# PoBoV1.net
KiCad netlist of a schematic drawn in EAGLE
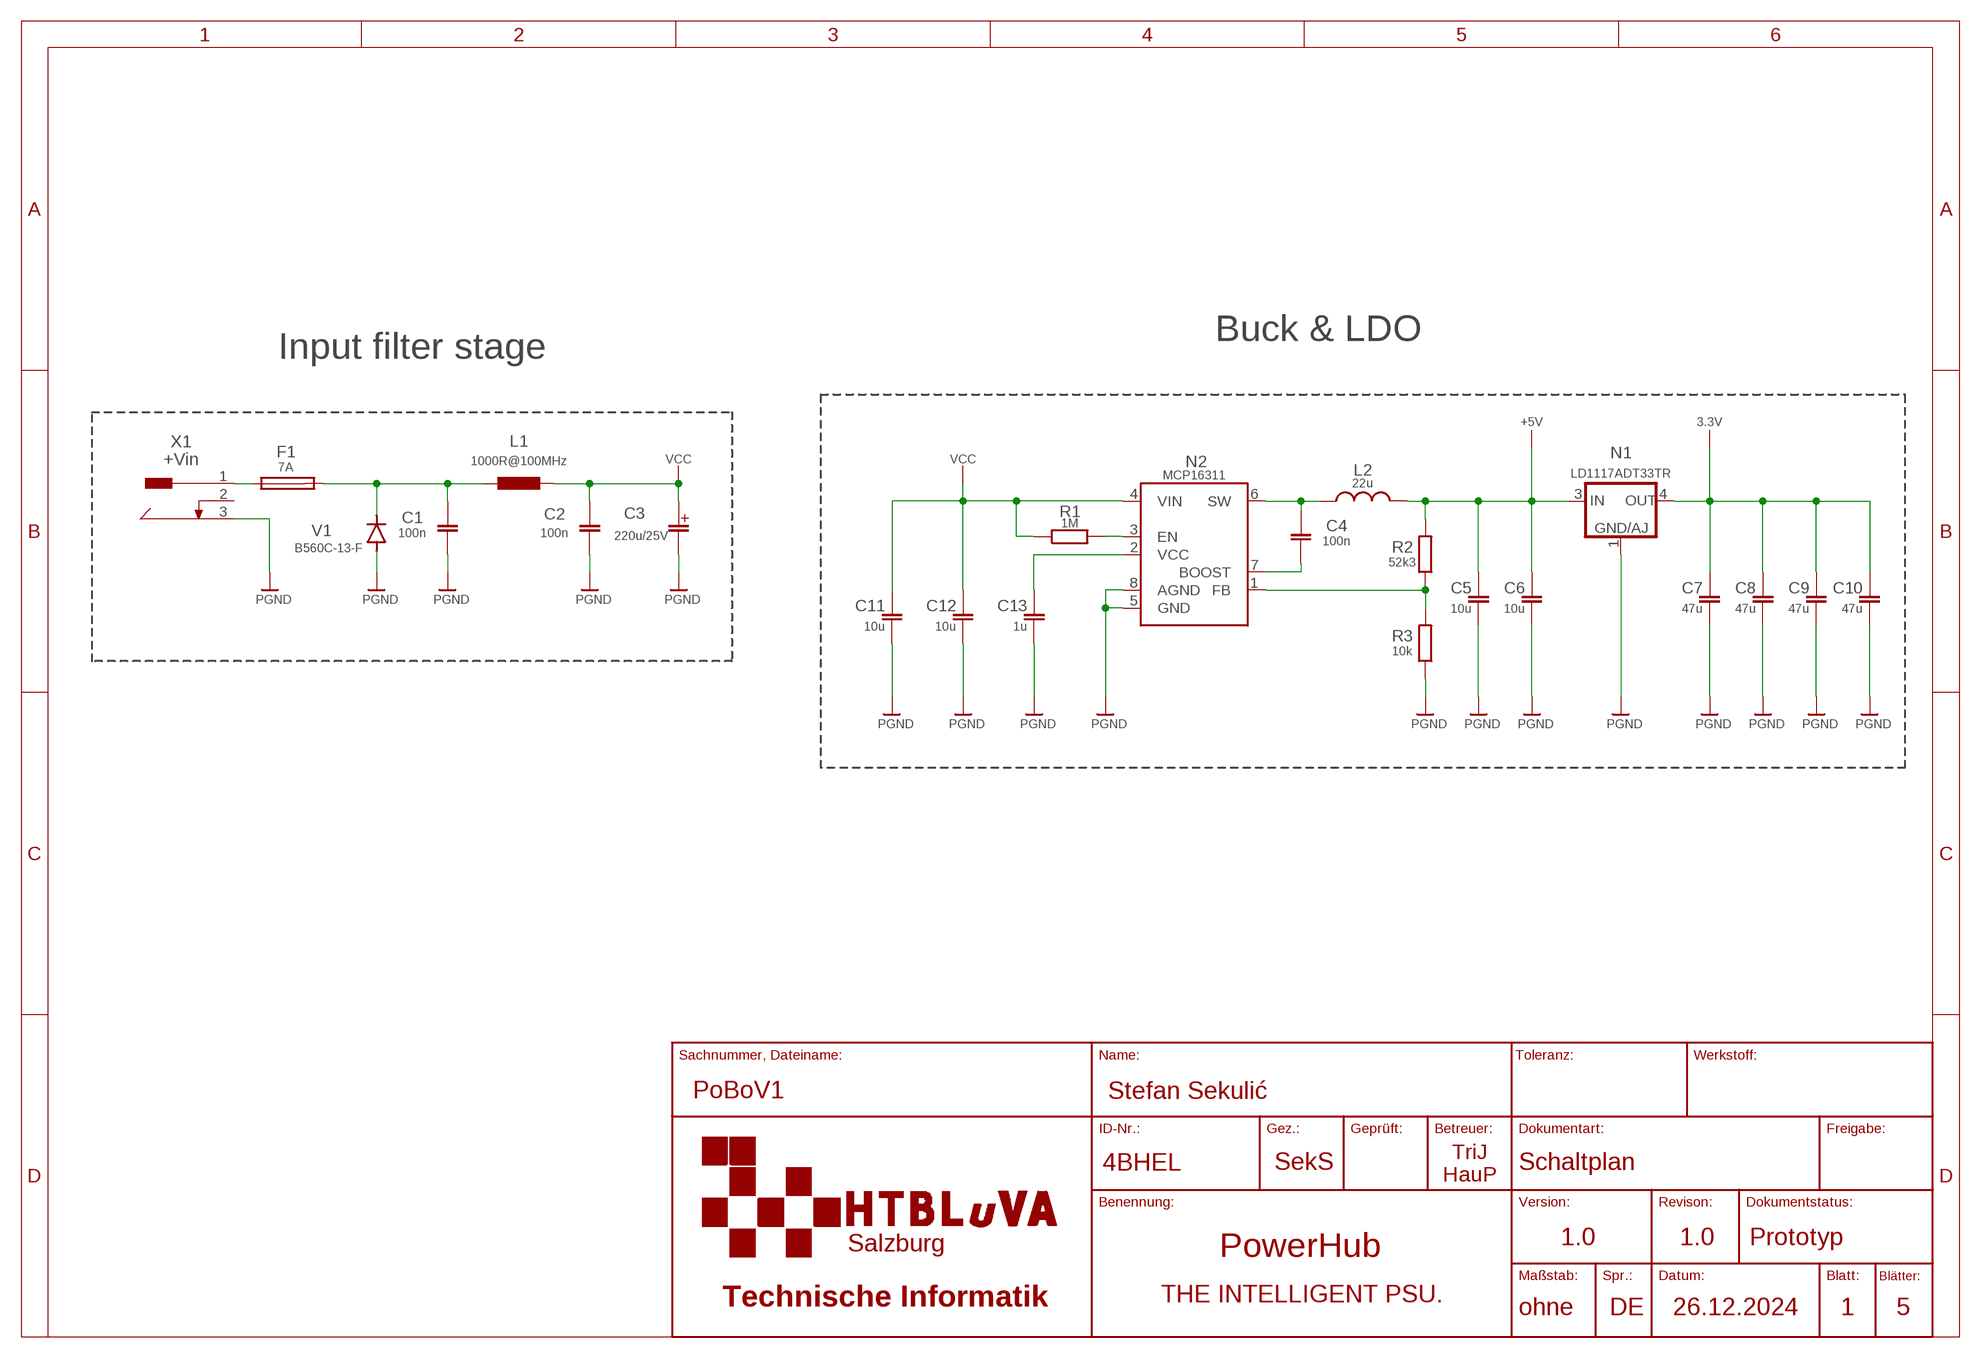
[diagram p0: schematic, sheet 1]
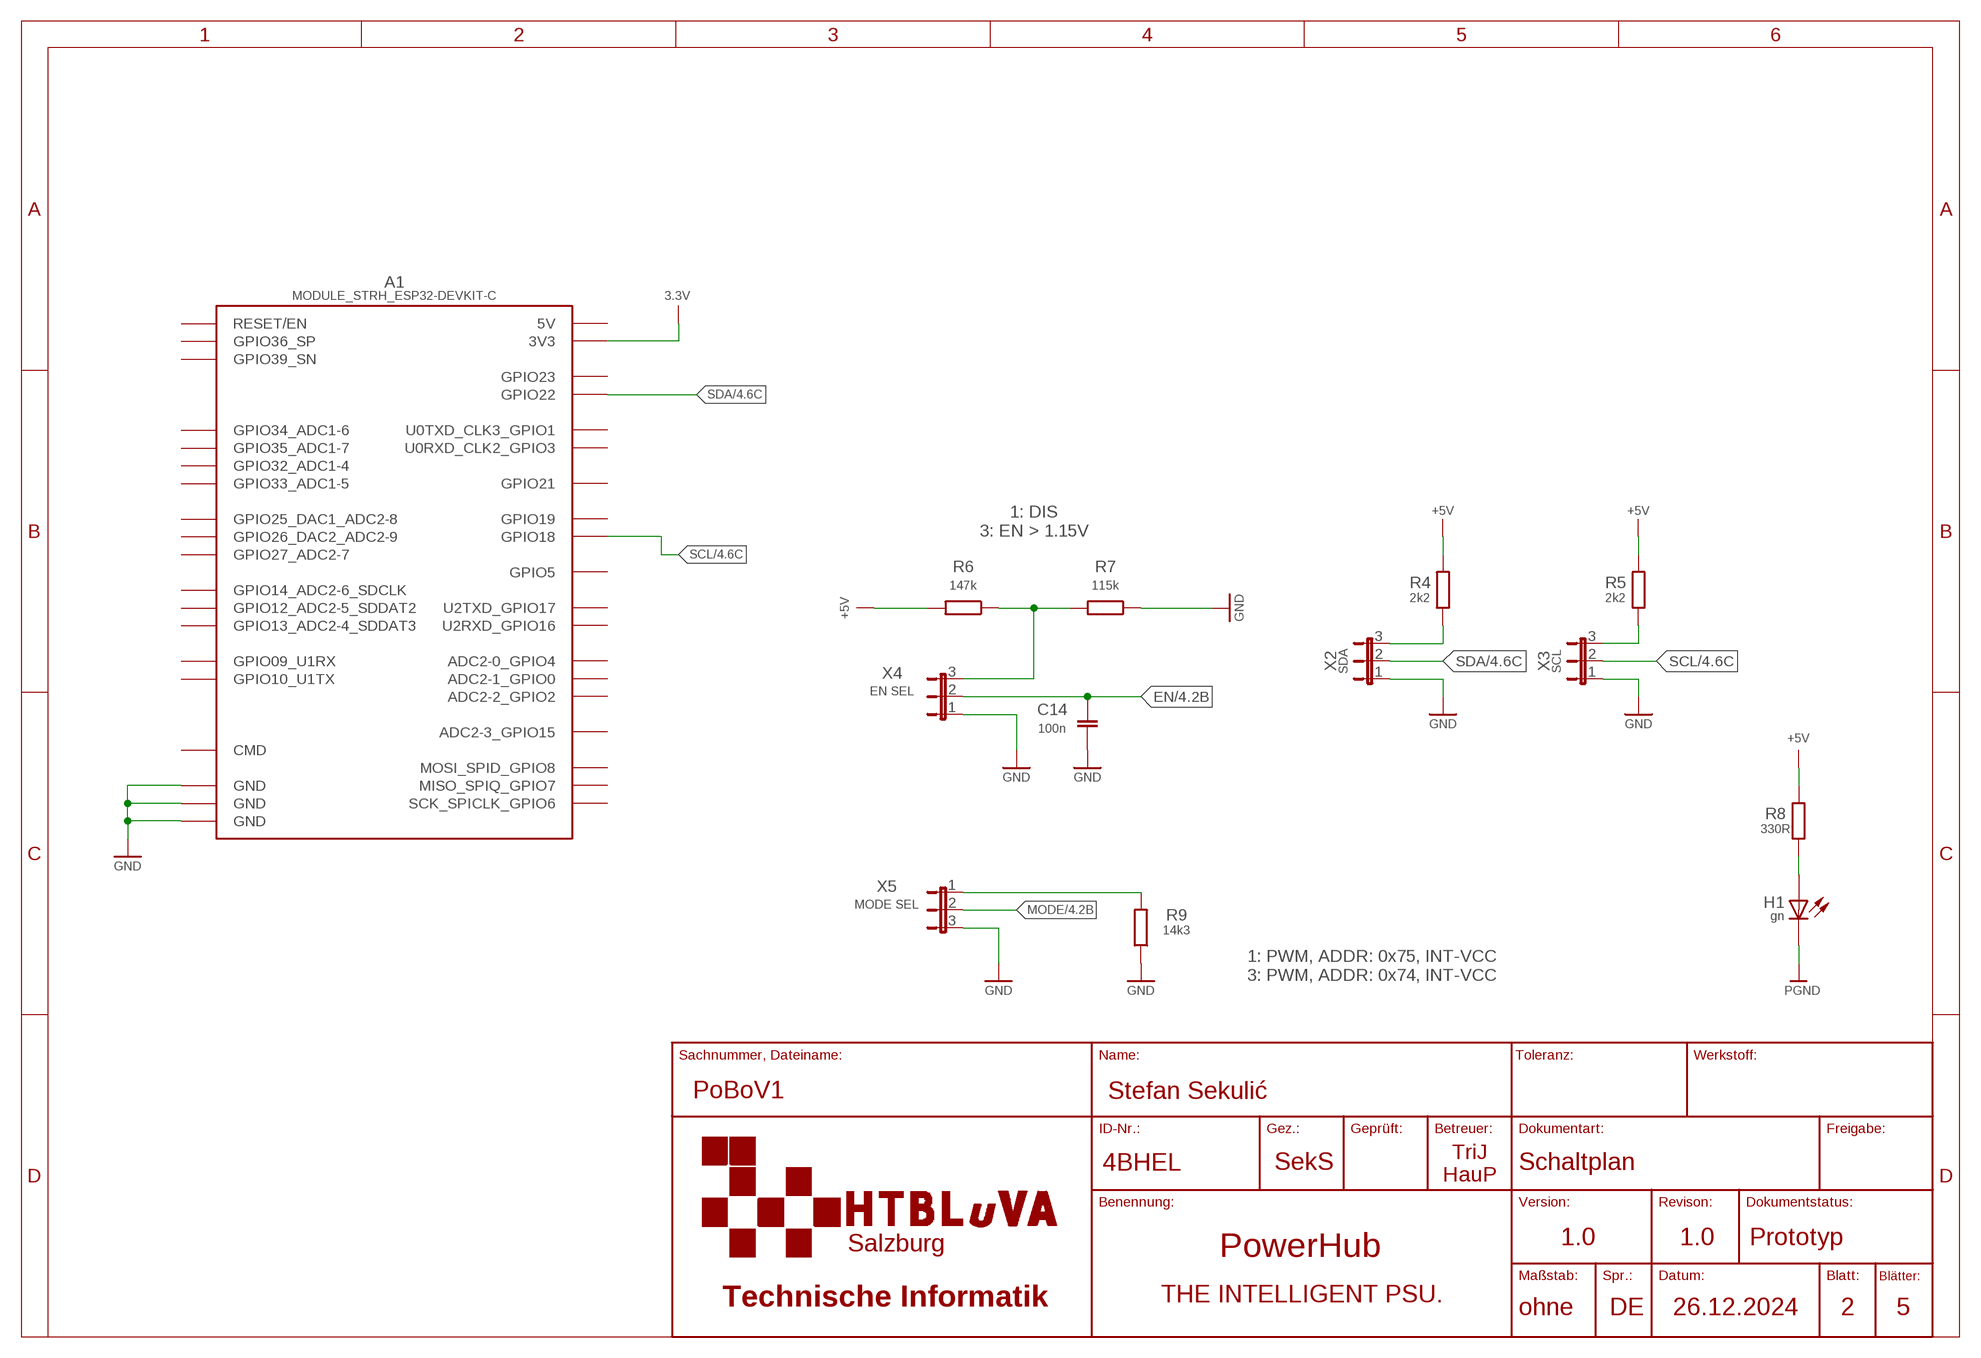
[diagram p1: schematic, sheet 2]
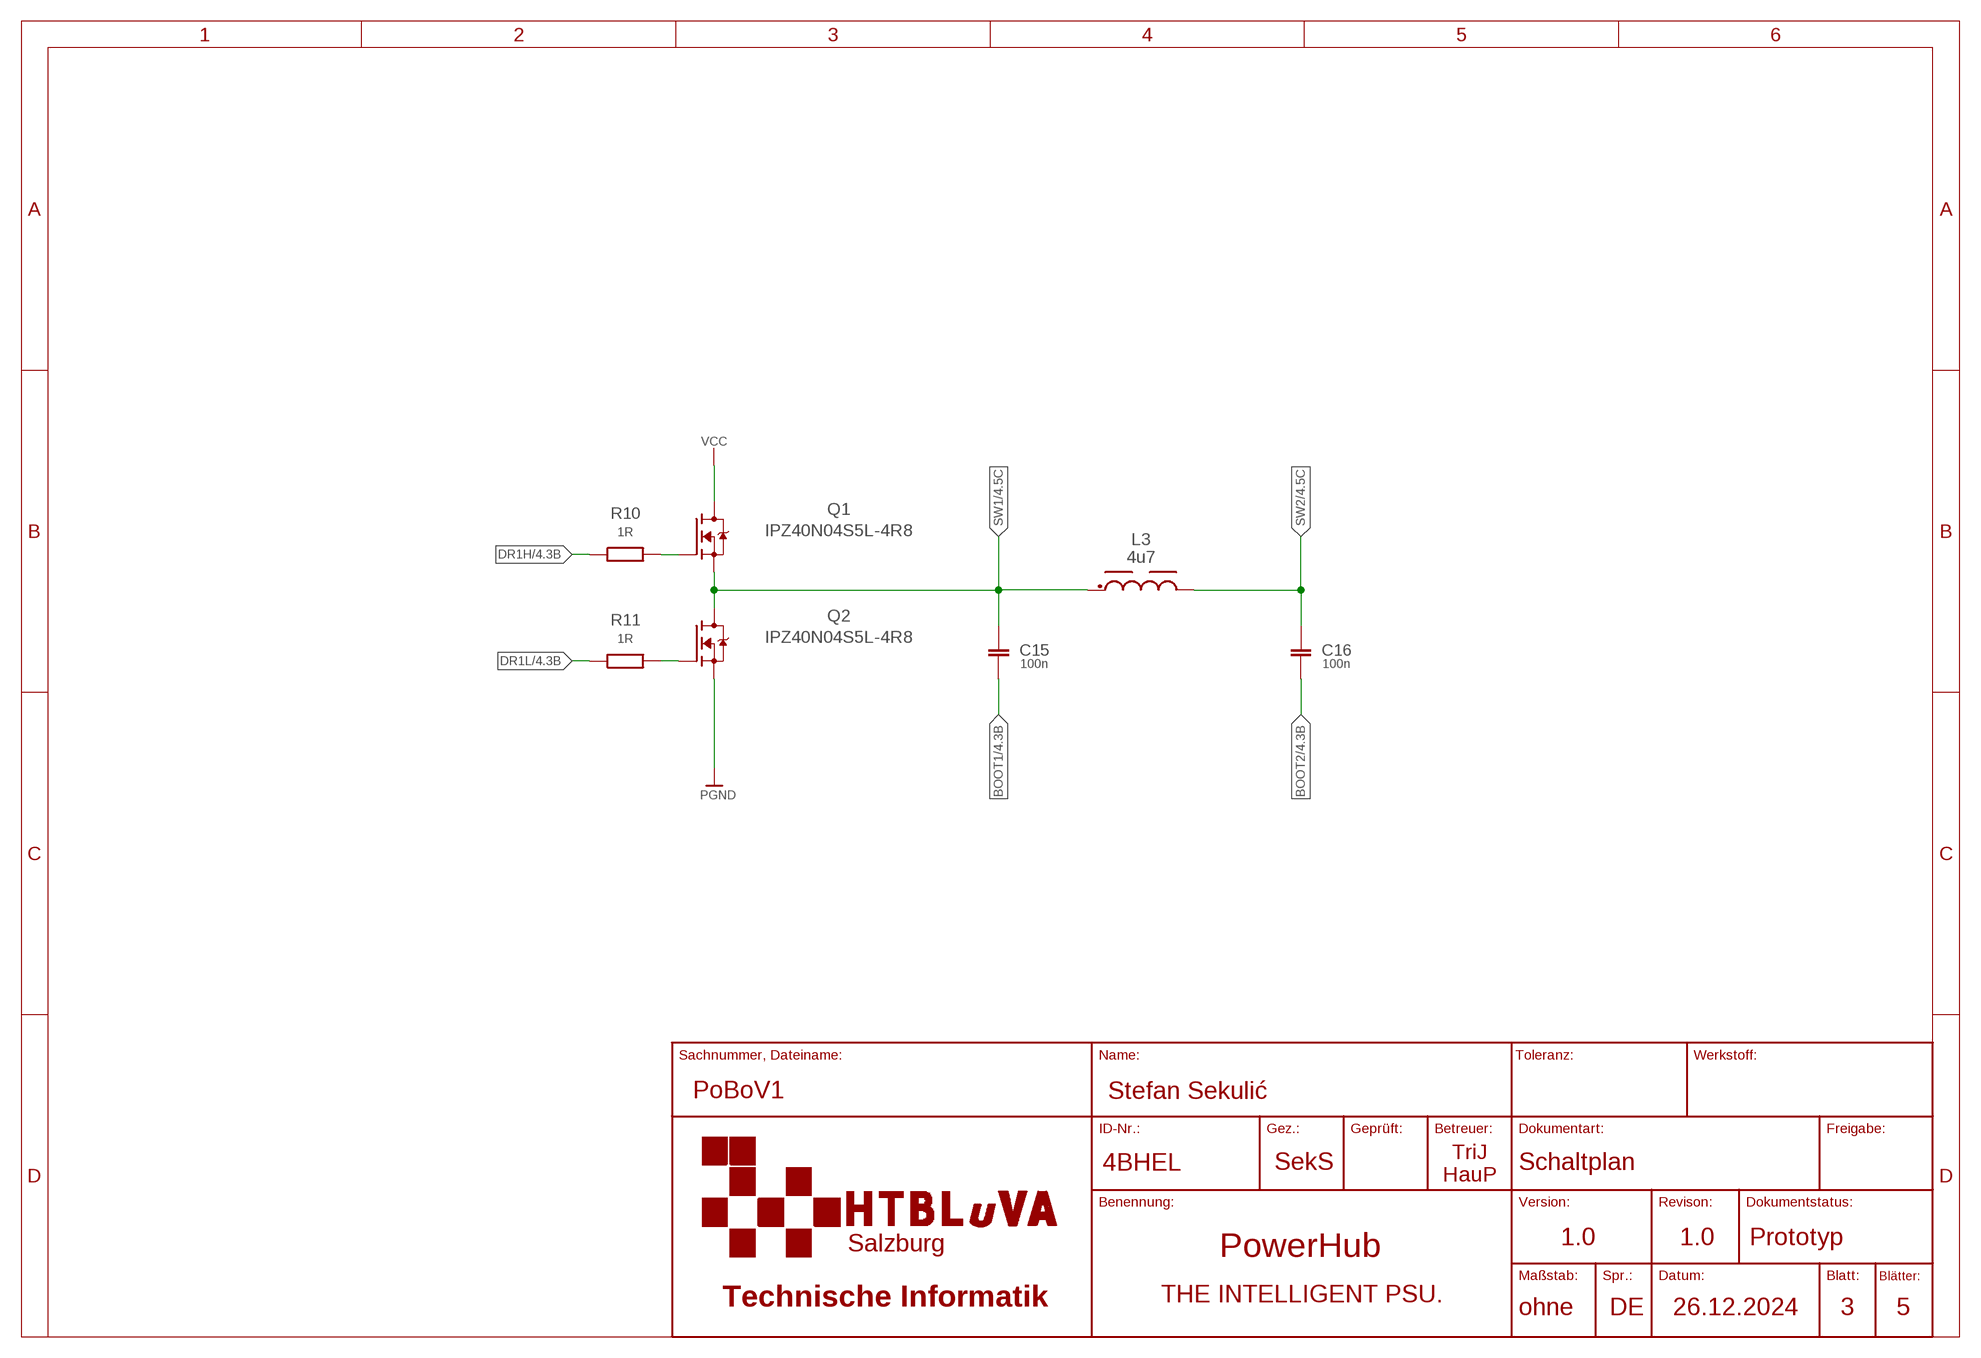
[diagram p2: schematic, sheet 3]
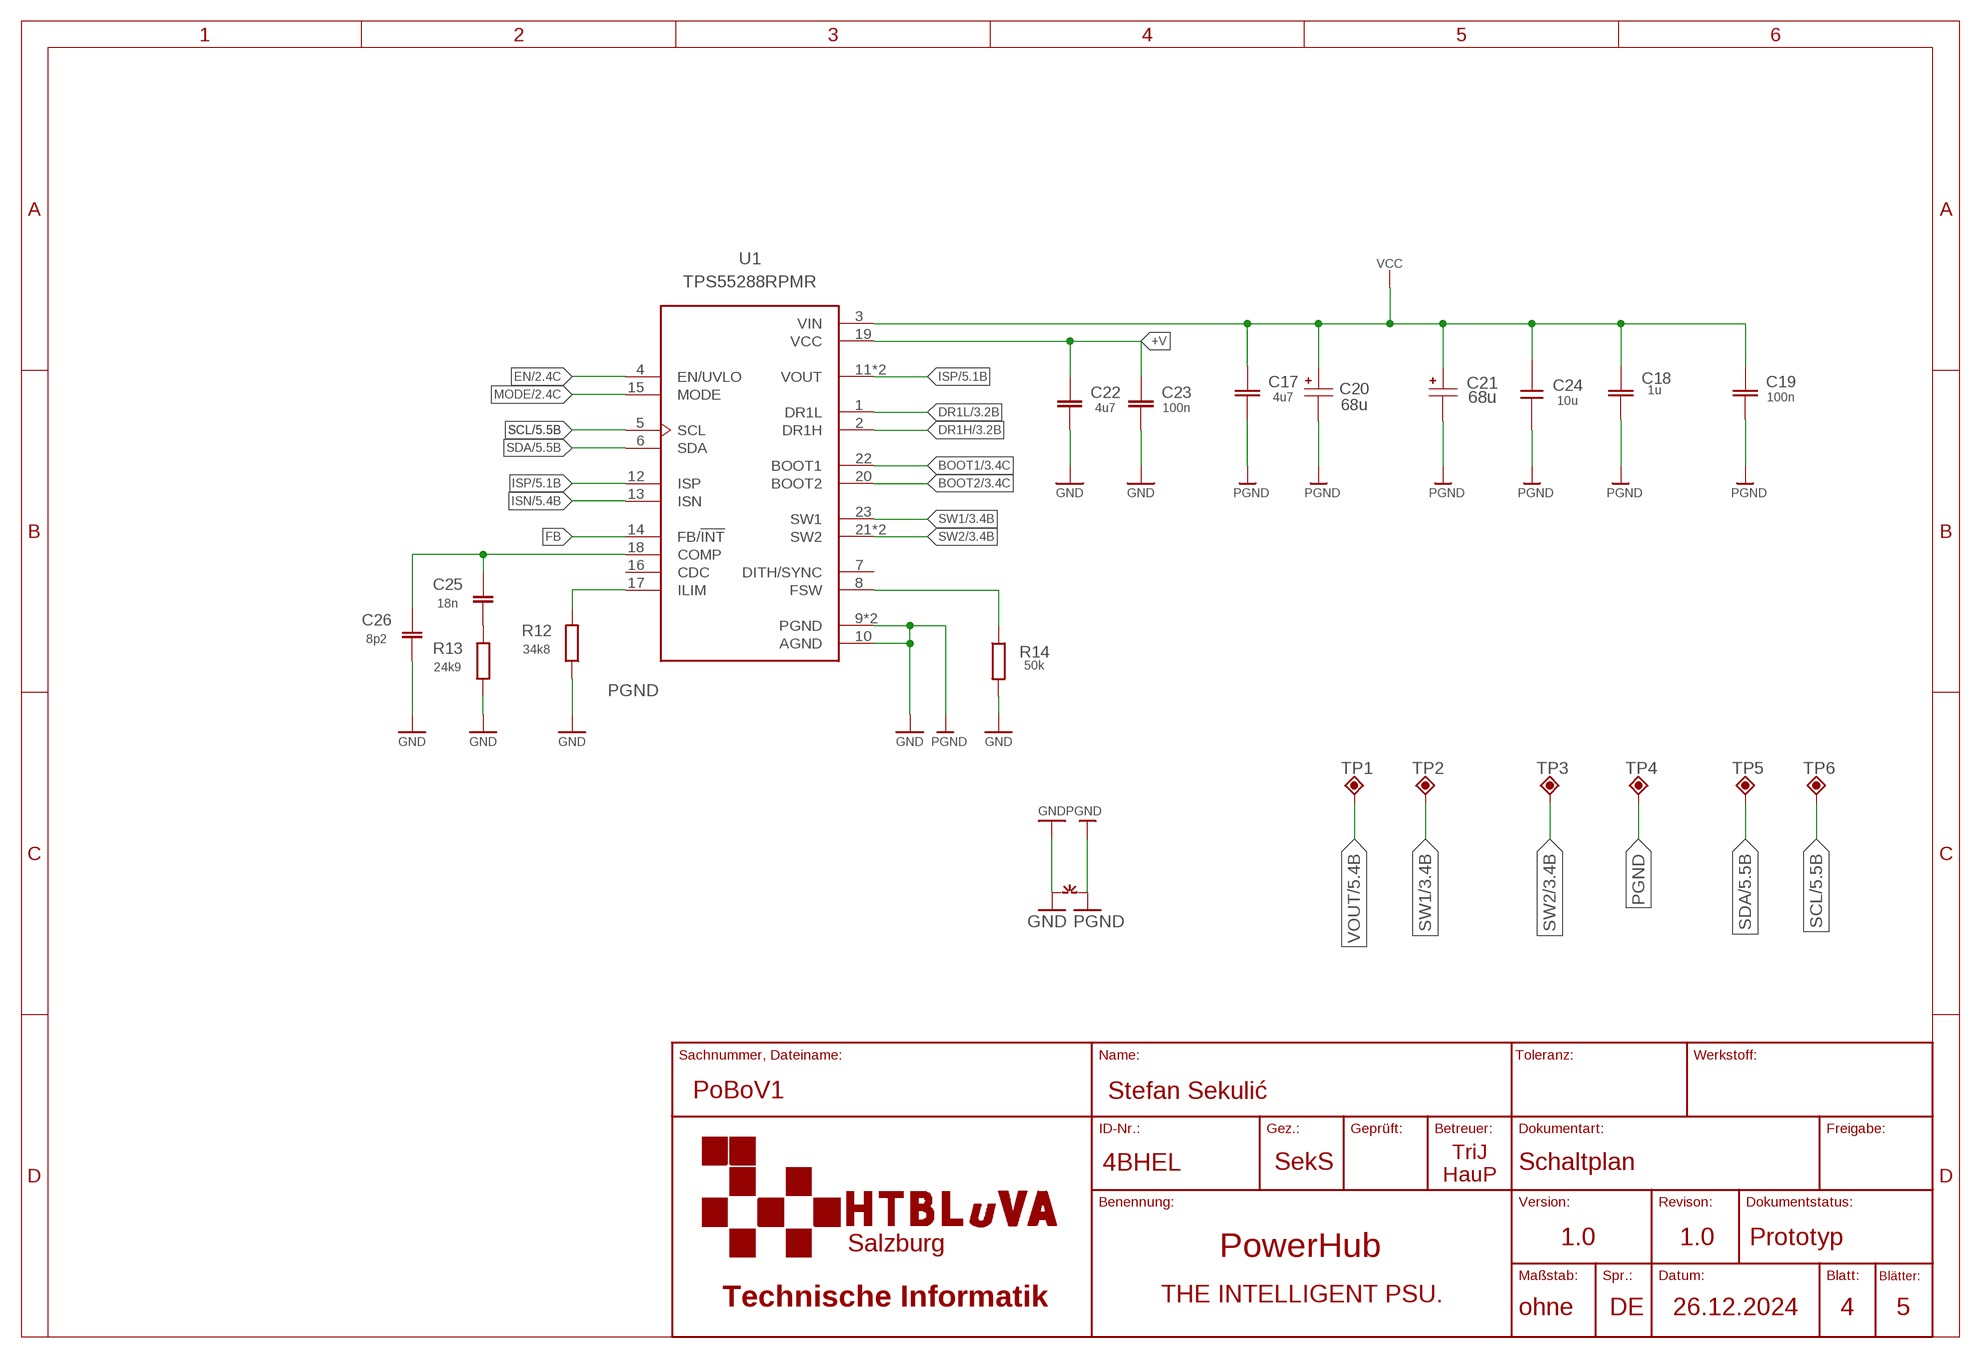
[diagram p3: schematic, sheet 4]
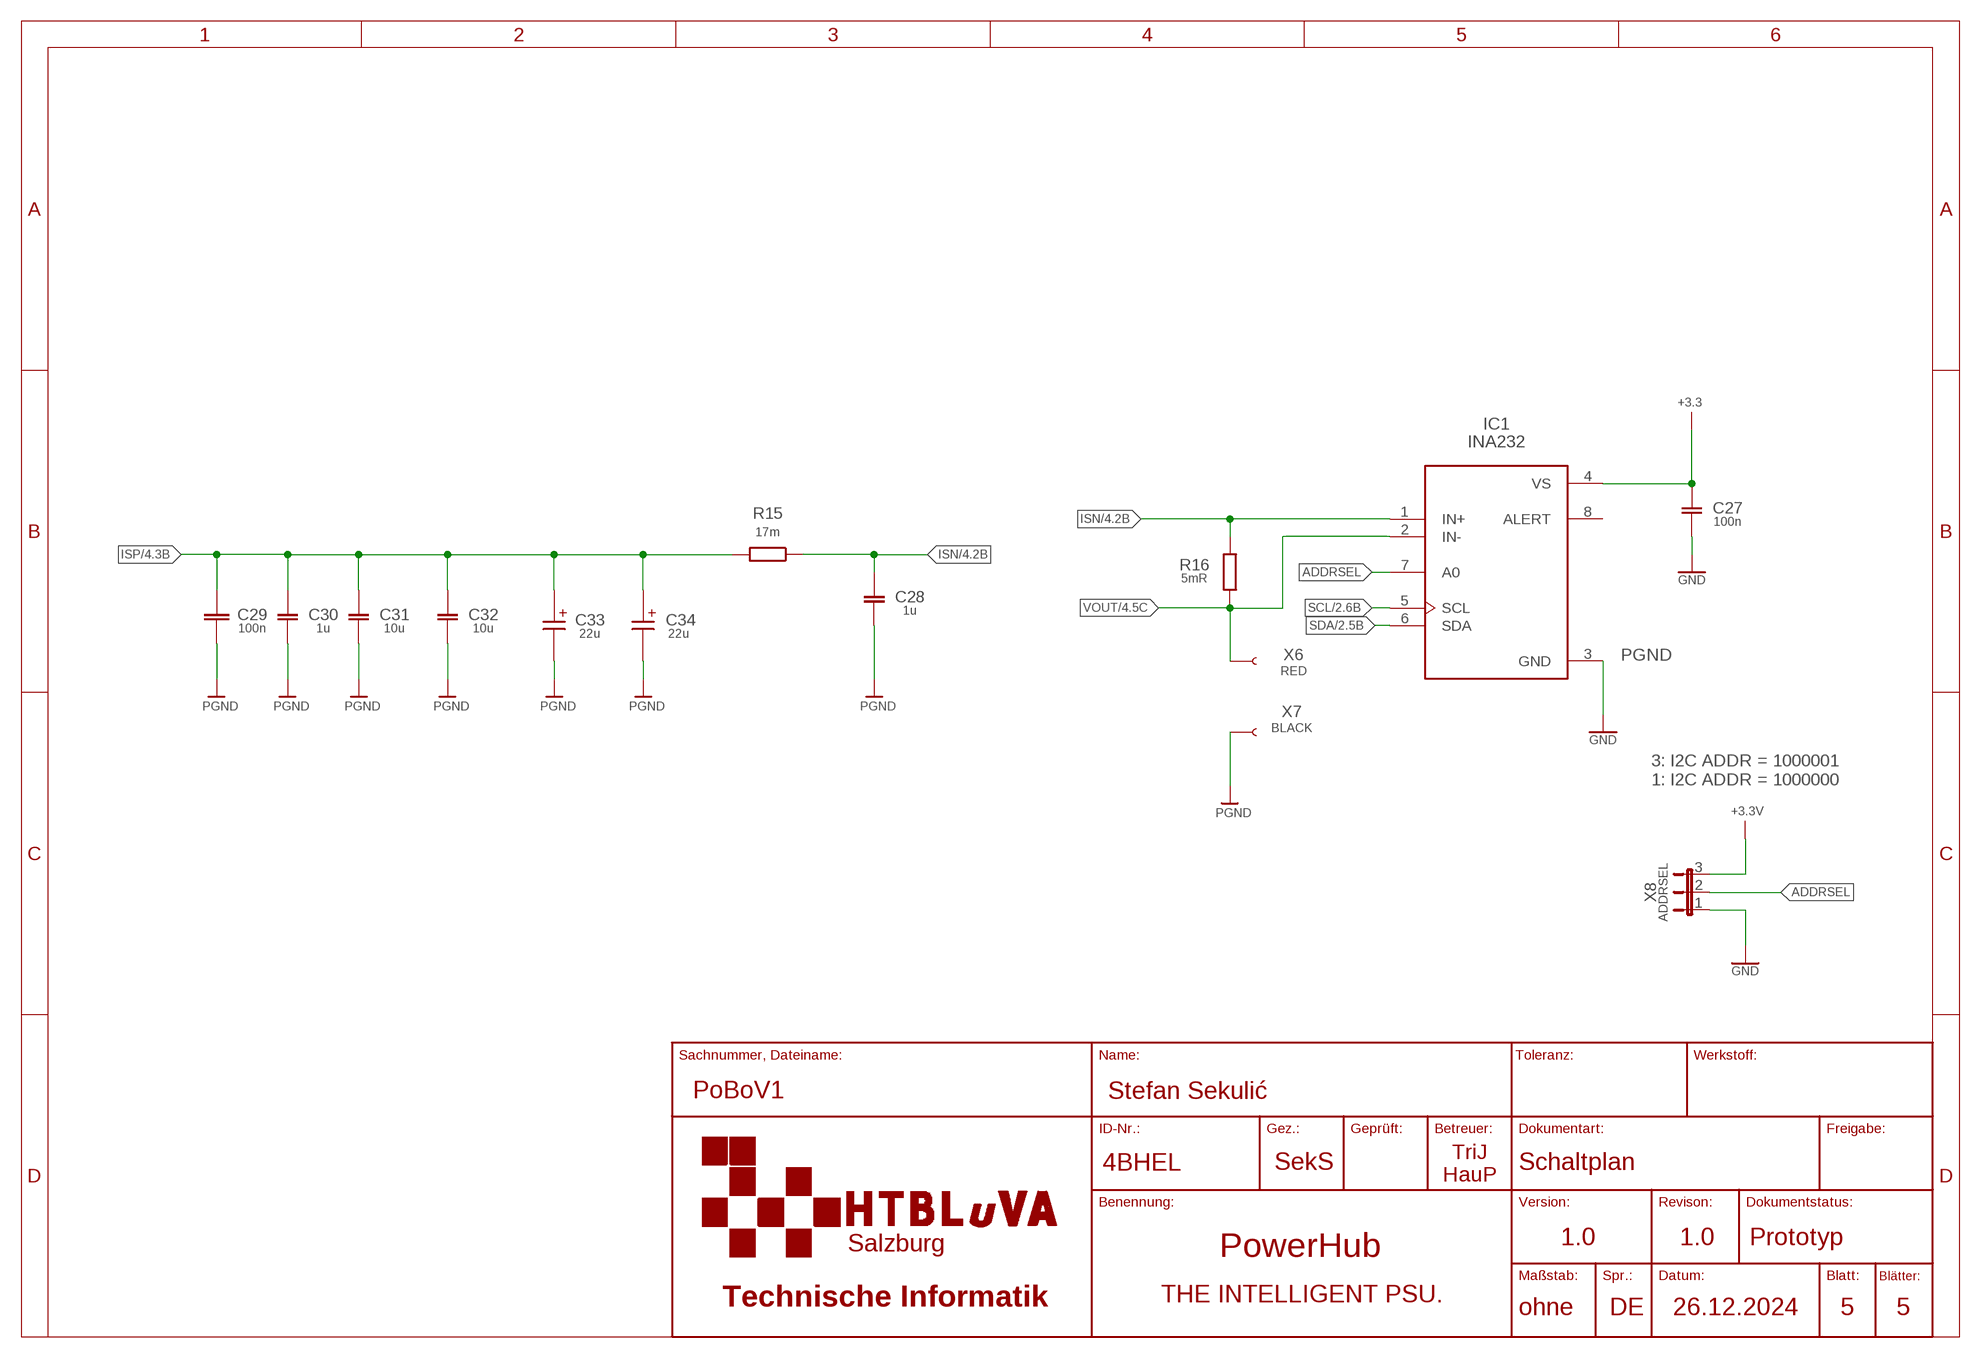
[diagram p4: schematic, sheet 5]

(export (version "E")
  (design (tool "Eeschema 10.0.6"))
  (components
    (comp (ref "C27")
      (value "100n")
      (footprint "eagle-import:MYLIB_C0805")
      (libsource (lib "eagle-import") (part "C-EUC0805"))
    )
    (comp (ref "C28")
      (value "1u")
      (footprint "eagle-import:MYLIB_C0805")
      (libsource (lib "eagle-import") (part "C-EUC0805"))
    )
    (comp (ref "C29")
      (value "100n")
      (footprint "eagle-import:MYRCL_C0402")
      (libsource (lib "eagle-import") (part "RCL_C-EUC0402"))
    )
    (comp (ref "C30")
      (value "1u")
      (footprint "eagle-import:MYLIB_C0805")
      (libsource (lib "eagle-import") (part "C-EUC0805"))
    )
    (comp (ref "C31")
      (value "10u")
      (footprint "eagle-import:MYLIB_C0805")
      (libsource (lib "eagle-import") (part "C-EUC0805"))
    )
    (comp (ref "C32")
      (value "10u")
      (footprint "eagle-import:MYLIB_C0805")
      (libsource (lib "eagle-import") (part "C-EUC0805"))
    )
    (comp (ref "C33")
      (value "22u")
      (footprint "eagle-import:PANASONIC_G")
      (libsource (lib "eagle-import") (part "C-POL_G"))
    )
    (comp (ref "C34")
      (value "22u")
      (footprint "eagle-import:PANASONIC_G")
      (libsource (lib "eagle-import") (part "C-POL_G"))
    )
    (comp (ref "IC1")
      (value "INA232")
      (footprint "eagle-import:SOT65P280X110-8N")
      (fields (field (name "MF") "Texas Instruments") (field (name "MP") "INA232AIDDFR"))
      (libsource (lib "eagle-import") (part "INA232AIDDFR"))
    )
    (comp (ref "R15")
      (value "17m")
      (footprint "eagle-import:R0805")
      (libsource (lib "eagle-import") (part "R-EU_R0805"))
    )
    (comp (ref "R16")
      (value "5mR")
      (footprint "eagle-import:RCL_STRH_R0805")
      (libsource (lib "eagle-import") (part "RCL_STRH_R-EU_R0805"))
    )
    (comp (ref "X6")
      (value "RED")
      (footprint "eagle-import:BANANAJACK")
      (libsource (lib "eagle-import") (part "BANANAJACKBANANAJACK-RED"))
    )
    (comp (ref "X7")
      (value "BLACK")
      (footprint "eagle-import:BANANAJACK")
      (libsource (lib "eagle-import") (part "BANANAJACKBANANAJACK-BLACK"))
    )
    (comp (ref "X8")
      (value "ADDRSEL")
      (footprint "eagle-import:JUMPER_JP3")
      (libsource (lib "eagle-import") (part "StefNe555_JUMPER_JP3EJP3E"))
    )
    (comp (ref "A1")
      (value "MODULE_STRH_ESP32-DEVKIT-C")
      (footprint "eagle-import:MODULE_STRH_DIL38-10_ESP")
      (libsource (lib "eagle-import") (part "MODULE_STRH_ESP32-DEVKIT-C"))
    )
    (comp (ref "C14")
      (value "100n")
      (footprint "eagle-import:C0805")
      (libsource (lib "eagle-import") (part "rcl_STRH_C-EUC0805"))
    )
    (comp (ref "H1")
      (value "gn")
      (footprint "eagle-import:CHIPLED_0805")
      (libsource (lib "eagle-import") (part "LEDCHIPLED_0805"))
    )
    (comp (ref "R4")
      (value "2k2")
      (footprint "eagle-import:R0805")
      (libsource (lib "eagle-import") (part "rcl_STRH_R-EU_R0805"))
    )
    (comp (ref "R5")
      (value "2k2")
      (footprint "eagle-import:R0805")
      (libsource (lib "eagle-import") (part "rcl_STRH_R-EU_R0805"))
    )
    (comp (ref "R6")
      (value "147k")
      (footprint "eagle-import:R0805")
      (libsource (lib "eagle-import") (part "rcl_STRH_R-EU_R0805"))
    )
    (comp (ref "R7")
      (value "115k")
      (footprint "eagle-import:R0805")
      (libsource (lib "eagle-import") (part "rcl_STRH_R-EU_R0805"))
    )
    (comp (ref "R8")
      (value "330R")
      (footprint "eagle-import:R0805")
      (libsource (lib "eagle-import") (part "rcl_STRH_R-EU_R0805"))
    )
    (comp (ref "R9")
      (value "14k3")
      (footprint "eagle-import:R0805")
      (libsource (lib "eagle-import") (part "rcl_STRH_R-EU_R0805"))
    )
    (comp (ref "X2")
      (value "SDA")
      (footprint "eagle-import:JUMPER_JP3")
      (libsource (lib "eagle-import") (part "JUMPER_JP3EJP3E"))
    )
    (comp (ref "X3")
      (value "SCL")
      (footprint "eagle-import:JUMPER_JP3")
      (libsource (lib "eagle-import") (part "JUMPER_JP3EJP3E"))
    )
    (comp (ref "X4")
      (value "EN SEL")
      (footprint "eagle-import:JUMPER_JP3")
      (libsource (lib "eagle-import") (part "JUMPER_JP3EJP3E"))
    )
    (comp (ref "X5")
      (value "MODE SEL")
      (footprint "eagle-import:JUMPER_JP3")
      (libsource (lib "eagle-import") (part "JUMPER_JP3EJP3E"))
    )
    (comp (ref "C17")
      (value "4u7")
      (footprint "eagle-import:MYRCL_C0603")
      (libsource (lib "eagle-import") (part "RCL_C-EUC0603"))
    )
    (comp (ref "C18")
      (value "1u")
      (footprint "eagle-import:MYRCL_C0603K")
      (libsource (lib "eagle-import") (part "RCL_C-EUC0603K"))
    )
    (comp (ref "C19")
      (value "100n")
      (footprint "eagle-import:MYRCL_C0402")
      (libsource (lib "eagle-import") (part "RCL_C-EUC0402"))
    )
    (comp (ref "C20")
      (value "68u")
      (footprint "eagle-import:CAP_EEHZA1H680P")
      (fields (field (name "MF") "Panasonic Electronic") (field (name "MP") "EEH-ZA1H680P"))
      (libsource (lib "eagle-import") (part "EEHZA1H680P"))
    )
    (comp (ref "C21")
      (value "68u")
      (footprint "eagle-import:CAP_EEHZA1H680P")
      (fields (field (name "MF") "Panasonic Electronic") (field (name "MP") "EEH-ZA1H680P"))
      (libsource (lib "eagle-import") (part "EEHZA1H680P"))
    )
    (comp (ref "C22")
      (value "4u7")
      (footprint "eagle-import:MYRCL_C0603")
      (libsource (lib "eagle-import") (part "RCL_C-EUC0603"))
    )
    (comp (ref "C23")
      (value "100n")
      (footprint "eagle-import:MYRCL_C0603")
      (libsource (lib "eagle-import") (part "RCL_C-EUC0603"))
    )
    (comp (ref "C24")
      (value "10u")
      (footprint "eagle-import:C1210")
      (libsource (lib "eagle-import") (part "C-EU_C1210"))
    )
    (comp (ref "C25")
      (value "18n")
      (footprint "eagle-import:MYLIB_C0805")
      (libsource (lib "eagle-import") (part "C-EUC0805"))
    )
    (comp (ref "C26")
      (value "8p2")
      (footprint "eagle-import:MYLIB_C0805")
      (libsource (lib "eagle-import") (part "C-EUC0805"))
    )
    (comp (ref "R12")
      (value "34k8")
      (footprint "eagle-import:R0805")
      (libsource (lib "eagle-import") (part "R-EU_R0805"))
    )
    (comp (ref "R13")
      (value "24k9")
      (footprint "eagle-import:R0805")
      (libsource (lib "eagle-import") (part "R-EU_R0805"))
    )
    (comp (ref "R14")
      (value "50k")
      (footprint "eagle-import:R0805")
      (libsource (lib "eagle-import") (part "R-EU_R0805"))
    )
    (comp (ref "TP1")
      (value "TPP-SMD-20SN")
      (footprint "eagle-import:SMD-20SN")
      (libsource (lib "eagle-import") (part "TPP-SMD-20SN"))
    )
    (comp (ref "TP2")
      (value "TPP-SMD-20SN")
      (footprint "eagle-import:SMD-20SN")
      (libsource (lib "eagle-import") (part "TPP-SMD-20SN"))
    )
    (comp (ref "TP3")
      (value "TPP-SMD-20SN")
      (footprint "eagle-import:SMD-20SN")
      (libsource (lib "eagle-import") (part "TPP-SMD-20SN"))
    )
    (comp (ref "TP4")
      (value "TPP-SMD-20SN")
      (footprint "eagle-import:SMD-20SN")
      (libsource (lib "eagle-import") (part "TPP-SMD-20SN"))
    )
    (comp (ref "TP5")
      (value "TPP-SMD-20SN")
      (footprint "eagle-import:SMD-20SN")
      (libsource (lib "eagle-import") (part "TPP-SMD-20SN"))
    )
    (comp (ref "TP6")
      (value "TPP-SMD-20SN")
      (footprint "eagle-import:SMD-20SN")
      (libsource (lib "eagle-import") (part "TPP-SMD-20SN"))
    )
    (comp (ref "U1")
      (value "TPS55288RPMR")
      (footprint "eagle-import:IC_TPS55288RPMR")
      (fields (field (name "MF") "Texas Instruments"))
      (libsource (lib "eagle-import") (part "TPS55288RPMR"))
    )
    (comp (ref "~NUDEV~1")
      (value "GND-GNDA")
      (footprint "eagle-import:GND-GNDA")
      (libsource (lib "eagle-import") (part "GND-GNDA"))
    )
    (comp (ref "C1")
      (value "100n")
      (footprint "eagle-import:C0805")
      (libsource (lib "eagle-import") (part "rcl_STRH_C-EUC0805"))
    )
    (comp (ref "C2")
      (value "100n")
      (footprint "eagle-import:C0805")
      (libsource (lib "eagle-import") (part "rcl_STRH_C-EUC0805"))
    )
    (comp (ref "C3")
      (value "220u/25V")
      (footprint "eagle-import:E2,5-6L")
      (libsource (lib "eagle-import") (part "CPOL-EUE2,5-6L"))
    )
    (comp (ref "C4")
      (value "100n")
      (footprint "eagle-import:C0805")
      (libsource (lib "eagle-import") (part "rcl_STRH_C-EUC0805"))
    )
    (comp (ref "C5")
      (value "10u")
      (footprint "eagle-import:C0805")
      (libsource (lib "eagle-import") (part "rcl_STRH_C-EUC0805"))
    )
    (comp (ref "C6")
      (value "10u")
      (footprint "eagle-import:C0805")
      (libsource (lib "eagle-import") (part "rcl_STRH_C-EUC0805"))
    )
    (comp (ref "C7")
      (value "47u")
      (footprint "eagle-import:C0805")
      (libsource (lib "eagle-import") (part "rcl_STRH_C-EUC0805"))
    )
    (comp (ref "C8")
      (value "47u")
      (footprint "eagle-import:C0805")
      (libsource (lib "eagle-import") (part "rcl_STRH_C-EUC0805"))
    )
    (comp (ref "C9")
      (value "47u")
      (footprint "eagle-import:C0805")
      (libsource (lib "eagle-import") (part "rcl_STRH_C-EUC0805"))
    )
    (comp (ref "C10")
      (value "47u")
      (footprint "eagle-import:C0805")
      (libsource (lib "eagle-import") (part "rcl_STRH_C-EUC0805"))
    )
    (comp (ref "C11")
      (value "10u")
      (footprint "eagle-import:C0805")
      (libsource (lib "eagle-import") (part "rcl_STRH_C-EUC0805"))
    )
    (comp (ref "C12")
      (value "10u")
      (footprint "eagle-import:C0805")
      (libsource (lib "eagle-import") (part "rcl_STRH_C-EUC0805"))
    )
    (comp (ref "C13")
      (value "1u")
      (footprint "eagle-import:C0805")
      (libsource (lib "eagle-import") (part "rcl_STRH_C-EUC0805"))
    )
    (comp (ref "F1")
      (value "7A")
      (footprint "eagle-import:TE5")
      (libsource (lib "eagle-import") (part "TE5"))
    )
    (comp (ref "L1")
      (value "1000R@100MHz")
      (footprint "eagle-import:0204_7@1")
      (fields (field (name "SPICEPREFIX") "L"))
      (libsource (lib "eagle-import") (part "L-EUL0204/7"))
    )
    (comp (ref "L2")
      (value "22u")
      (footprint "eagle-import:WE-TPC_5818_5828")
      (libsource (lib "eagle-import") (part "SPULETPC5818"))
    )
    (comp (ref "N1")
      (value "LD1117ADT33TR")
      (footprint "eagle-import:DPACK")
      (libsource (lib "eagle-import") (part "LD1117A?DT33TR"))
    )
    (comp (ref "N2")
      (value "MCP16311")
      (footprint "eagle-import:MSOP8")
      (libsource (lib "eagle-import") (part "MCP16311"))
    )
    (comp (ref "R1")
      (value "1M")
      (footprint "eagle-import:R0805")
      (libsource (lib "eagle-import") (part "rcl_STRH_R-EU_R0805"))
    )
    (comp (ref "R2")
      (value "52k3")
      (footprint "eagle-import:R0805")
      (libsource (lib "eagle-import") (part "rcl_STRH_R-EU_R0805"))
    )
    (comp (ref "R3")
      (value "10k")
      (footprint "eagle-import:R0805")
      (libsource (lib "eagle-import") (part "rcl_STRH_R-EU_R0805"))
    )
    (comp (ref "V1")
      (value "B560C-13-F")
      (footprint "eagle-import:SMC")
      (fields (field (name "MF") "Diodes Inc."))
      (libsource (lib "eagle-import") (part "B560C-13-F"))
    )
    (comp (ref "X1")
      (value "+Vin")
      (footprint "eagle-import:DCJ0202")
      (libsource (lib "eagle-import") (part "DCJ0202"))
    )
    (comp (ref "C15")
      (value "100n")
      (footprint "eagle-import:MYLIB_C0805")
      (libsource (lib "eagle-import") (part "C-EUC0805"))
    )
    (comp (ref "C16")
      (value "100n")
      (footprint "eagle-import:MYLIB_C0805")
      (libsource (lib "eagle-import") (part "C-EUC0805"))
    )
    (comp (ref "L3")
      (value "4u7")
      (footprint "eagle-import:WE-PD_1280P")
      (fields (field (name "MF") "Wurth Elektronik") (field (name "MP") "7447707047"))
      (libsource (lib "eagle-import") (part "WE-PD_1280P"))
    )
    (comp (ref "Q1")
      (value "IPZ40N04S5L-4R8")
      (footprint "eagle-import:TRANS_BSZ100N06LS3_G")
      (fields (field (name "MF") "Infineon") (field (name "MP") "BSZ100N06LS3 G"))
      (libsource (lib "eagle-import") (part "BSZ100N06LS3_G"))
    )
    (comp (ref "Q2")
      (value "IPZ40N04S5L-4R8")
      (footprint "eagle-import:TRANS_BSZ100N06LS3_G")
      (fields (field (name "MF") "Infineon") (field (name "MP") "BSZ100N06LS3 G"))
      (libsource (lib "eagle-import") (part "BSZ100N06LS3_G"))
    )
    (comp (ref "R10")
      (value "1R")
      (footprint "eagle-import:R0805")
      (libsource (lib "eagle-import") (part "R-EU_R0805"))
    )
    (comp (ref "R11")
      (value "1R")
      (footprint "eagle-import:R0805")
      (libsource (lib "eagle-import") (part "R-EU_R0805"))
    )
  )
  (nets
    (net (code "1") (name "+3.3") (class "Default")
      (node (ref "A1") (pin "3V3") (pinfunction "3V3_3V3") (pintype "bidirectional"))
      (node (ref "C10") (pin "1") (pinfunction "1_1") (pintype "passive"))
      (node (ref "C27") (pin "1") (pinfunction "1_1") (pintype "passive"))
      (node (ref "C7") (pin "1") (pinfunction "1_1") (pintype "passive"))
      (node (ref "C8") (pin "1") (pinfunction "1_1") (pintype "passive"))
      (node (ref "C9") (pin "1") (pinfunction "1_1") (pintype "passive"))
      (node (ref "IC1") (pin "4") (pinfunction "VS_4") (pintype "power_in"))
      (node (ref "N1") (pin "4") (pinfunction "OUT_4") (pintype "passive"))
    )
    (net (code "2") (name "+3.3V") (class "Default")
      (node (ref "X8") (pin "3") (pinfunction "3_3") (pintype "passive"))
    )
    (net (code "3") (name "+5V") (class "Default")
      (node (ref "C5") (pin "1") (pinfunction "1_1") (pintype "passive"))
      (node (ref "C6") (pin "1") (pinfunction "1_1") (pintype "passive"))
      (node (ref "L2") (pin "2") (pinfunction "2_2") (pintype "passive"))
      (node (ref "N1") (pin "3") (pinfunction "IN_3") (pintype "input"))
      (node (ref "R2") (pin "2") (pinfunction "2_2") (pintype "passive"))
      (node (ref "R4") (pin "2") (pinfunction "2_2") (pintype "passive"))
      (node (ref "R5") (pin "2") (pinfunction "2_2") (pintype "passive"))
      (node (ref "R6") (pin "2") (pinfunction "2_2") (pintype "passive"))
      (node (ref "R8") (pin "2") (pinfunction "2_2") (pintype "passive"))
    )
    (net (code "4") (name "+V") (class "Default")
      (node (ref "C22") (pin "1") (pinfunction "1_1") (pintype "passive"))
      (node (ref "C23") (pin "1") (pinfunction "1_1") (pintype "passive"))
      (node (ref "U1") (pin "19") (pinfunction "VCC_19") (pintype "power_in"))
    )
    (net (code "5") (name "ADDRSEL") (class "Default")
      (node (ref "IC1") (pin "7") (pinfunction "A0_7") (pintype "input"))
      (node (ref "X8") (pin "2") (pinfunction "2_2") (pintype "passive"))
    )
    (net (code "6") (name "BOOT1") (class "Default")
      (node (ref "C15") (pin "2") (pinfunction "2_2") (pintype "passive"))
      (node (ref "U1") (pin "22") (pinfunction "BOOT1_22") (pintype "input"))
    )
    (net (code "7") (name "BOOT2") (class "Default")
      (node (ref "C16") (pin "2") (pinfunction "2_2") (pintype "passive"))
      (node (ref "U1") (pin "20") (pinfunction "BOOT2_20") (pintype "output"))
    )
    (net (code "8") (name "DR1H") (class "Default")
      (node (ref "R10") (pin "1") (pinfunction "1_1") (pintype "passive"))
      (node (ref "U1") (pin "2") (pinfunction "DR1H_2") (pintype "output"))
    )
    (net (code "9") (name "DR1L") (class "Default")
      (node (ref "R11") (pin "1") (pinfunction "1_1") (pintype "passive"))
      (node (ref "U1") (pin "1") (pinfunction "DR1L_1") (pintype "output"))
    )
    (net (code "10") (name "EN") (class "Default")
      (node (ref "C14") (pin "1") (pinfunction "1_1") (pintype "passive"))
      (node (ref "U1") (pin "4") (pinfunction "EN/UVLO_4") (pintype "input"))
      (node (ref "X4") (pin "2") (pinfunction "2_2") (pintype "passive"))
    )
    (net (code "11") (name "FB") (class "Default")
      (node (ref "U1") (pin "14") (pinfunction "FB/~{INT}_14") (pintype "bidirectional"))
    )
    (net (code "12") (name "ISN") (class "Default")
      (node (ref "C28") (pin "1") (pinfunction "1_1") (pintype "passive"))
      (node (ref "IC1") (pin "1") (pinfunction "IN+_1") (pintype "input"))
      (node (ref "R15") (pin "1") (pinfunction "1_1") (pintype "passive"))
      (node (ref "R16") (pin "2") (pinfunction "2_2") (pintype "passive"))
      (node (ref "U1") (pin "13") (pinfunction "ISN_13") (pintype "input"))
    )
    (net (code "13") (name "ISP") (class "Default")
      (node (ref "C29") (pin "1") (pinfunction "1_1") (pintype "passive"))
      (node (ref "C30") (pin "1") (pinfunction "1_1") (pintype "passive"))
      (node (ref "C31") (pin "1") (pinfunction "1_1") (pintype "passive"))
      (node (ref "C32") (pin "1") (pinfunction "1_1") (pintype "passive"))
      (node (ref "C33") (pin "+") (pinfunction "+_+") (pintype "passive"))
      (node (ref "C34") (pin "+") (pinfunction "+_+") (pintype "passive"))
      (node (ref "R15") (pin "2") (pinfunction "2_2") (pintype "passive"))
      (node (ref "U1") (pin "11") (pinfunction "VOUT_11") (pintype "output"))
      (node (ref "U1") (pin "12") (pinfunction "ISP_12") (pintype "input"))
      (node (ref "U1") (pin "26") (pinfunction "VOUT_26") (pintype "output"))
    )
    (net (code "14") (name "MODE") (class "Default")
      (node (ref "U1") (pin "15") (pinfunction "MODE_15") (pintype "input"))
      (node (ref "X5") (pin "2") (pinfunction "2_2") (pintype "passive"))
    )
    (net (code "15") (name "Net-(C1-Pad1)") (class "Default")
      (node (ref "C1") (pin "1") (pinfunction "1_1") (pintype "passive"))
      (node (ref "F1") (pin "2") (pinfunction "2_2") (pintype "passive"))
      (node (ref "L1") (pin "1") (pinfunction "1_1") (pintype "passive"))
      (node (ref "V1") (pin "C") (pinfunction "C_C") (pintype "passive"))
    )
    (net (code "16") (name "Net-(C25-Pad2)") (class "Default")
      (node (ref "C25") (pin "2") (pinfunction "2_2") (pintype "passive"))
      (node (ref "R13") (pin "2") (pinfunction "2_2") (pintype "passive"))
    )
    (net (code "17") (name "Net-(F1-Pad1)") (class "Default")
      (node (ref "F1") (pin "1") (pinfunction "1_1") (pintype "passive"))
      (node (ref "X1") (pin "1") (pinfunction "1_1") (pintype "passive"))
    )
    (net (code "18") (name "Net-(H1-PadA)") (class "Default")
      (node (ref "H1") (pin "A") (pinfunction "A_A") (pintype "passive"))
      (node (ref "R8") (pin "1") (pinfunction "1_1") (pintype "passive"))
    )
    (net (code "19") (name "Net-(N2-BOOST)") (class "Default")
      (node (ref "C4") (pin "2") (pinfunction "2_2") (pintype "passive"))
      (node (ref "N2") (pin "7") (pinfunction "BOOST_7") (pintype "bidirectional"))
    )
    (net (code "20") (name "Net-(N2-EN)") (class "Default")
      (node (ref "N2") (pin "3") (pinfunction "EN_3") (pintype "bidirectional"))
      (node (ref "R1") (pin "2") (pinfunction "2_2") (pintype "passive"))
    )
    (net (code "21") (name "Net-(N2-FB)") (class "Default")
      (node (ref "N2") (pin "1") (pinfunction "FB_1") (pintype "input"))
      (node (ref "R2") (pin "1") (pinfunction "1_1") (pintype "passive"))
      (node (ref "R3") (pin "2") (pinfunction "2_2") (pintype "passive"))
    )
    (net (code "22") (name "Net-(N2-SW)") (class "Default")
      (node (ref "C4") (pin "1") (pinfunction "1_1") (pintype "passive"))
      (node (ref "L2") (pin "1") (pinfunction "1_1") (pintype "passive"))
      (node (ref "N2") (pin "6") (pinfunction "SW_6") (pintype "bidirectional"))
    )
    (net (code "23") (name "Net-(N2-VCC)") (class "Default")
      (node (ref "C13") (pin "1") (pinfunction "1_1") (pintype "passive"))
      (node (ref "N2") (pin "2") (pinfunction "VCC_2") (pintype "bidirectional"))
    )
    (net (code "24") (name "Net-(Q1-G)") (class "Default")
      (node (ref "Q1") (pin "4") (pinfunction "G_4") (pintype "passive"))
      (node (ref "R10") (pin "2") (pinfunction "2_2") (pintype "passive"))
    )
    (net (code "25") (name "Net-(Q2-G)") (class "Default")
      (node (ref "Q2") (pin "4") (pinfunction "G_4") (pintype "passive"))
      (node (ref "R11") (pin "2") (pinfunction "2_2") (pintype "passive"))
    )
    (net (code "26") (name "Net-(R4-Pad1)") (class "Default")
      (node (ref "R4") (pin "1") (pinfunction "1_1") (pintype "passive"))
      (node (ref "X2") (pin "3") (pinfunction "3_3") (pintype "passive"))
    )
    (net (code "27") (name "Net-(R5-Pad1)") (class "Default")
      (node (ref "R5") (pin "1") (pinfunction "1_1") (pintype "passive"))
      (node (ref "X3") (pin "3") (pinfunction "3_3") (pintype "passive"))
    )
    (net (code "28") (name "Net-(R6-Pad1)") (class "Default")
      (node (ref "R6") (pin "1") (pinfunction "1_1") (pintype "passive"))
      (node (ref "R7") (pin "2") (pinfunction "2_2") (pintype "passive"))
      (node (ref "X4") (pin "3") (pinfunction "3_3") (pintype "passive"))
    )
    (net (code "29") (name "Net-(R9-Pad2)") (class "Default")
      (node (ref "R9") (pin "2") (pinfunction "2_2") (pintype "passive"))
      (node (ref "X5") (pin "1") (pinfunction "1_1") (pintype "passive"))
    )
    (net (code "30") (name "Net-(U1-COMP)") (class "Default")
      (node (ref "C25") (pin "1") (pinfunction "1_1") (pintype "passive"))
      (node (ref "C26") (pin "1") (pinfunction "1_1") (pintype "passive"))
      (node (ref "U1") (pin "18") (pinfunction "COMP_18") (pintype "input"))
    )
    (net (code "31") (name "Net-(U1-FSW)") (class "Default")
      (node (ref "R14") (pin "1") (pinfunction "1_1") (pintype "passive"))
      (node (ref "U1") (pin "8") (pinfunction "FSW_8") (pintype "output"))
    )
    (net (code "32") (name "Net-(U1-ILIM)") (class "Default")
      (node (ref "R12") (pin "2") (pinfunction "2_2") (pintype "passive"))
      (node (ref "U1") (pin "17") (pinfunction "ILIM_17") (pintype "bidirectional"))
    )
    (net (code "33") (name "PGND") (class "Default")
      (node (ref "A1") (pin "GND") (pinfunction "GND_GND") (pintype "bidirectional"))
      (node (ref "A1") (pin "GND@1") (pinfunction "GND_GND@1") (pintype "bidirectional"))
      (node (ref "A1") (pin "GND@2") (pinfunction "GND_GND@2") (pintype "bidirectional"))
      (node (ref "C1") (pin "2") (pinfunction "2_2") (pintype "passive"))
      (node (ref "C10") (pin "2") (pinfunction "2_2") (pintype "passive"))
      (node (ref "C11") (pin "2") (pinfunction "2_2") (pintype "passive"))
      (node (ref "C12") (pin "2") (pinfunction "2_2") (pintype "passive"))
      (node (ref "C13") (pin "2") (pinfunction "2_2") (pintype "passive"))
      (node (ref "C14") (pin "2") (pinfunction "2_2") (pintype "passive"))
      (node (ref "C17") (pin "2") (pinfunction "2_2") (pintype "passive"))
      (node (ref "C18") (pin "2") (pinfunction "2_2") (pintype "passive"))
      (node (ref "C19") (pin "2") (pinfunction "2_2") (pintype "passive"))
      (node (ref "C2") (pin "2") (pinfunction "2_2") (pintype "passive"))
      (node (ref "C20") (pin "2") (pinfunction "2_2") (pintype "passive"))
      (node (ref "C21") (pin "2") (pinfunction "2_2") (pintype "passive"))
      (node (ref "C22") (pin "2") (pinfunction "2_2") (pintype "passive"))
      (node (ref "C23") (pin "2") (pinfunction "2_2") (pintype "passive"))
      (node (ref "C24") (pin "2") (pinfunction "2_2") (pintype "passive"))
      (node (ref "C26") (pin "2") (pinfunction "2_2") (pintype "passive"))
      (node (ref "C27") (pin "2") (pinfunction "2_2") (pintype "passive"))
      (node (ref "C28") (pin "2") (pinfunction "2_2") (pintype "passive"))
      (node (ref "C29") (pin "2") (pinfunction "2_2") (pintype "passive"))
      (node (ref "C3") (pin "-") (pinfunction "-_-") (pintype "passive"))
      (node (ref "C30") (pin "2") (pinfunction "2_2") (pintype "passive"))
      (node (ref "C31") (pin "2") (pinfunction "2_2") (pintype "passive"))
      (node (ref "C32") (pin "2") (pinfunction "2_2") (pintype "passive"))
      (node (ref "C33") (pin "-") (pinfunction "-_-") (pintype "passive"))
      (node (ref "C34") (pin "-") (pinfunction "-_-") (pintype "passive"))
      (node (ref "C5") (pin "2") (pinfunction "2_2") (pintype "passive"))
      (node (ref "C6") (pin "2") (pinfunction "2_2") (pintype "passive"))
      (node (ref "C7") (pin "2") (pinfunction "2_2") (pintype "passive"))
      (node (ref "C8") (pin "2") (pinfunction "2_2") (pintype "passive"))
      (node (ref "C9") (pin "2") (pinfunction "2_2") (pintype "passive"))
      (node (ref "H1") (pin "C") (pinfunction "C_C") (pintype "passive"))
      (node (ref "IC1") (pin "3") (pinfunction "GND_3") (pintype "power_in"))
      (node (ref "N1") (pin "1") (pinfunction "GND/ADJ_1") (pintype "input"))
      (node (ref "N2") (pin "5") (pinfunction "GND_5") (pintype "bidirectional"))
      (node (ref "N2") (pin "8") (pinfunction "AGND_8") (pintype "bidirectional"))
      (node (ref "Q2") (pin "1") (pinfunction "S_1") (pintype "passive"))
      (node (ref "Q2") (pin "2") (pinfunction "S_2") (pintype "passive"))
      (node (ref "Q2") (pin "3") (pinfunction "S_3") (pintype "passive"))
      (node (ref "R12") (pin "1") (pinfunction "1_1") (pintype "passive"))
      (node (ref "R13") (pin "1") (pinfunction "1_1") (pintype "passive"))
      (node (ref "R14") (pin "2") (pinfunction "2_2") (pintype "passive"))
      (node (ref "R3") (pin "1") (pinfunction "1_1") (pintype "passive"))
      (node (ref "R7") (pin "1") (pinfunction "1_1") (pintype "passive"))
      (node (ref "R9") (pin "1") (pinfunction "1_1") (pintype "passive"))
      (node (ref "TP4") (pin "TP") (pinfunction "P_TP") (pintype "passive"))
      (node (ref "U1") (pin "10") (pinfunction "AGND_10") (pintype "power_in"))
      (node (ref "U1") (pin "24") (pinfunction "PGND_24") (pintype "power_in"))
      (node (ref "U1") (pin "9") (pinfunction "PGND_9") (pintype "power_in"))
      (node (ref "V1") (pin "A") (pinfunction "A_A") (pintype "passive"))
      (node (ref "X1") (pin "3") (pinfunction "3_3") (pintype "passive"))
      (node (ref "X2") (pin "1") (pinfunction "1_1") (pintype "passive"))
      (node (ref "X3") (pin "1") (pinfunction "1_1") (pintype "passive"))
      (node (ref "X4") (pin "1") (pinfunction "1_1") (pintype "passive"))
      (node (ref "X5") (pin "3") (pinfunction "3_3") (pintype "passive"))
      (node (ref "X7") (pin "P$1") (pinfunction "2_P$1") (pintype "passive"))
      (node (ref "X8") (pin "1") (pinfunction "1_1") (pintype "passive"))
      (node (ref "~NUDEV~1") (pin "GND") (pinfunction "GND_GND") (pintype "power_in"))
      (node (ref "~NUDEV~1") (pin "PGND") (pinfunction "GNDA_PGND") (pintype "power_in"))
    )
    (net (code "34") (name "SCL") (class "Default")
      (node (ref "A1") (pin "GPIO18") (pinfunction "GPIO18_GPIO18") (pintype "bidirectional"))
      (node (ref "IC1") (pin "5") (pinfunction "SCL_5") (pintype "input"))
      (node (ref "TP6") (pin "TP") (pinfunction "P_TP") (pintype "passive"))
      (node (ref "U1") (pin "5") (pinfunction "SCL_5") (pintype "input"))
      (node (ref "X3") (pin "2") (pinfunction "2_2") (pintype "passive"))
    )
    (net (code "35") (name "SDA") (class "Default")
      (node (ref "A1") (pin "GPIO22") (pinfunction "GPIO22_GPIO22") (pintype "bidirectional"))
      (node (ref "IC1") (pin "6") (pinfunction "SDA_6") (pintype "bidirectional"))
      (node (ref "TP5") (pin "TP") (pinfunction "P_TP") (pintype "passive"))
      (node (ref "U1") (pin "6") (pinfunction "SDA_6") (pintype "bidirectional"))
      (node (ref "X2") (pin "2") (pinfunction "2_2") (pintype "passive"))
    )
    (net (code "36") (name "SW1") (class "Default")
      (node (ref "C15") (pin "1") (pinfunction "1_1") (pintype "passive"))
      (node (ref "L3") (pin "1") (pinfunction "1_1") (pintype "passive"))
      (node (ref "Q1") (pin "1") (pinfunction "S_1") (pintype "passive"))
      (node (ref "Q1") (pin "2") (pinfunction "S_2") (pintype "passive"))
      (node (ref "Q1") (pin "3") (pinfunction "S_3") (pintype "passive"))
      (node (ref "Q2") (pin "5_8") (pinfunction "D_5_8") (pintype "passive"))
      (node (ref "TP2") (pin "TP") (pinfunction "P_TP") (pintype "passive"))
      (node (ref "U1") (pin "23") (pinfunction "SW1_23") (pintype "input"))
    )
    (net (code "37") (name "SW2") (class "Default")
      (node (ref "C16") (pin "1") (pinfunction "1_1") (pintype "passive"))
      (node (ref "L3") (pin "2") (pinfunction "2_2") (pintype "passive"))
      (node (ref "TP3") (pin "TP") (pinfunction "P_TP") (pintype "passive"))
      (node (ref "U1") (pin "21") (pinfunction "SW2_21") (pintype "input"))
      (node (ref "U1") (pin "25") (pinfunction "SW2_25") (pintype "input"))
    )
    (net (code "38") (name "VCC") (class "Default")
      (node (ref "C11") (pin "1") (pinfunction "1_1") (pintype "passive"))
      (node (ref "C12") (pin "1") (pinfunction "1_1") (pintype "passive"))
      (node (ref "C17") (pin "1") (pinfunction "1_1") (pintype "passive"))
      (node (ref "C18") (pin "1") (pinfunction "1_1") (pintype "passive"))
      (node (ref "C19") (pin "1") (pinfunction "1_1") (pintype "passive"))
      (node (ref "C2") (pin "1") (pinfunction "1_1") (pintype "passive"))
      (node (ref "C20") (pin "1") (pinfunction "1_1") (pintype "passive"))
      (node (ref "C21") (pin "1") (pinfunction "1_1") (pintype "passive"))
      (node (ref "C24") (pin "1") (pinfunction "1_1") (pintype "passive"))
      (node (ref "C3") (pin "+") (pinfunction "+_+") (pintype "passive"))
      (node (ref "L1") (pin "2") (pinfunction "2_2") (pintype "passive"))
      (node (ref "N2") (pin "4") (pinfunction "VIN_4") (pintype "input"))
      (node (ref "Q1") (pin "5_8") (pinfunction "D_5_8") (pintype "passive"))
      (node (ref "R1") (pin "1") (pinfunction "1_1") (pintype "passive"))
      (node (ref "U1") (pin "3") (pinfunction "VIN_3") (pintype "power_in"))
    )
    (net (code "39") (name "VOUT") (class "Default")
      (node (ref "IC1") (pin "2") (pinfunction "IN-_2") (pintype "input"))
      (node (ref "R16") (pin "1") (pinfunction "1_1") (pintype "passive"))
      (node (ref "TP1") (pin "TP") (pinfunction "P_TP") (pintype "passive"))
      (node (ref "X6") (pin "P$1") (pinfunction "2_P$1") (pintype "passive"))
    )
    (net (code "40") (name "unconnected-(A1-ADC2-0_GPIO4-PadGPIO04)") (class "Default")
      (node (ref "A1") (pin "GPIO04") (pinfunction "ADC2-0_GPIO4_GPIO04") (pintype "bidirectional"))
    )
    (net (code "41") (name "unconnected-(A1-ADC2-1_GPIO0-PadGPIO00)") (class "Default")
      (node (ref "A1") (pin "GPIO00") (pinfunction "ADC2-1_GPIO0_GPIO00") (pintype "bidirectional"))
    )
    (net (code "42") (name "unconnected-(A1-ADC2-2_GPIO2-PadGPIO02)") (class "Default")
      (node (ref "A1") (pin "GPIO02") (pinfunction "ADC2-2_GPIO2_GPIO02") (pintype "bidirectional"))
    )
    (net (code "43") (name "unconnected-(A1-ADC2-3_GPIO15-PadGPIO15)") (class "Default")
      (node (ref "A1") (pin "GPIO15") (pinfunction "ADC2-3_GPIO15_GPIO15") (pintype "bidirectional"))
    )
    (net (code "44") (name "unconnected-(A1-GPIO5-PadGPIO05)") (class "Default")
      (node (ref "A1") (pin "GPIO05") (pinfunction "GPIO5_GPIO05") (pintype "bidirectional"))
    )
    (net (code "45") (name "unconnected-(A1-GPIO09_U1RX-PadGPIO09)") (class "Default")
      (node (ref "A1") (pin "GPIO09") (pinfunction "GPIO09_U1RX_GPIO09") (pintype "bidirectional"))
    )
    (net (code "46") (name "unconnected-(A1-GPIO10_U1TX-PadGPIO10)") (class "Default")
      (node (ref "A1") (pin "GPIO10") (pinfunction "GPIO10_U1TX_GPIO10") (pintype "bidirectional"))
    )
    (net (code "47") (name "unconnected-(A1-GPIO12_ADC2-5_SDDAT2-PadGPIO12)") (class "Default")
      (node (ref "A1") (pin "GPIO12") (pinfunction "GPIO12_ADC2-5_SDDAT2_GPIO12") (pintype "bidirectional"))
    )
    (net (code "48") (name "unconnected-(A1-GPIO13_ADC2-4_SDDAT3-PadGPIO13)") (class "Default")
      (node (ref "A1") (pin "GPIO13") (pinfunction "GPIO13_ADC2-4_SDDAT3_GPIO13") (pintype "bidirectional"))
    )
    (net (code "49") (name "unconnected-(A1-GPIO14_ADC2-6_SDCLK-PadGPIO14)") (class "Default")
      (node (ref "A1") (pin "GPIO14") (pinfunction "GPIO14_ADC2-6_SDCLK_GPIO14") (pintype "bidirectional"))
    )
    (net (code "50") (name "unconnected-(A1-GPIO25_DAC1_ADC2-8-PadGPIO25)") (class "Default")
      (node (ref "A1") (pin "GPIO25") (pinfunction "GPIO25_DAC1_ADC2-8_GPIO25") (pintype "bidirectional"))
    )
    (net (code "51") (name "unconnected-(A1-GPIO26_DAC2_ADC2-9-PadGPIO26)") (class "Default")
      (node (ref "A1") (pin "GPIO26") (pinfunction "GPIO26_DAC2_ADC2-9_GPIO26") (pintype "bidirectional"))
    )
    (net (code "52") (name "unconnected-(A1-GPIO27_ADC2-7-PadGPIO27)") (class "Default")
      (node (ref "A1") (pin "GPIO27") (pinfunction "GPIO27_ADC2-7_GPIO27") (pintype "bidirectional"))
    )
    (net (code "53") (name "unconnected-(A1-GPIO32_ADC1-4-PadGPIO32)") (class "Default")
      (node (ref "A1") (pin "GPIO32") (pinfunction "GPIO32_ADC1-4_GPIO32") (pintype "bidirectional"))
    )
    (net (code "54") (name "unconnected-(A1-GPIO33_ADC1-5-PadGPIO33)") (class "Default")
      (node (ref "A1") (pin "GPIO33") (pinfunction "GPIO33_ADC1-5_GPIO33") (pintype "bidirectional"))
    )
    (net (code "55") (name "unconnected-(A1-GPIO34_ADC1-6-PadGPIO34)") (class "Default")
      (node (ref "A1") (pin "GPIO34") (pinfunction "GPIO34_ADC1-6_GPIO34") (pintype "bidirectional"))
    )
    (net (code "56") (name "unconnected-(A1-GPIO35_ADC1-7-PadGPIO35)") (class "Default")
      (node (ref "A1") (pin "GPIO35") (pinfunction "GPIO35_ADC1-7_GPIO35") (pintype "bidirectional"))
    )
    (net (code "57") (name "unconnected-(A1-GPIO36_SP-PadSP)") (class "Default")
      (node (ref "A1") (pin "SP") (pinfunction "GPIO36_SP_SP") (pintype "bidirectional"))
    )
    (net (code "58") (name "unconnected-(A1-GPIO39_SN-PadSN)") (class "Default")
      (node (ref "A1") (pin "SN") (pinfunction "GPIO39_SN_SN") (pintype "bidirectional"))
    )
    (net (code "59") (name "unconnected-(A1-MISO_SPIQ_GPIO7-PadGPIO07)") (class "Default")
      (node (ref "A1") (pin "GPIO07") (pinfunction "MISO_SPIQ_GPIO7_GPIO07") (pintype "bidirectional"))
    )
    (net (code "60") (name "unconnected-(A1-MOSI_SPID_GPIO8-PadGPIO08)") (class "Default")
      (node (ref "A1") (pin "GPIO08") (pinfunction "MOSI_SPID_GPIO8_GPIO08") (pintype "bidirectional"))
    )
    (net (code "61") (name "unconnected-(A1-Pad5V)") (class "Default")
      (node (ref "A1") (pin "5V") (pinfunction "5V_5V") (pintype "bidirectional"))
    )
    (net (code "62") (name "unconnected-(A1-PadCMD)") (class "Default")
      (node (ref "A1") (pin "CMD") (pinfunction "CMD_CMD") (pintype "bidirectional"))
    )
    (net (code "63") (name "unconnected-(A1-PadGPIO19)") (class "Default")
      (node (ref "A1") (pin "GPIO19") (pinfunction "GPIO19_GPIO19") (pintype "bidirectional"))
    )
    (net (code "64") (name "unconnected-(A1-PadGPIO21)") (class "Default")
      (node (ref "A1") (pin "GPIO21") (pinfunction "GPIO21_GPIO21") (pintype "bidirectional"))
    )
    (net (code "65") (name "unconnected-(A1-PadGPIO23)") (class "Default")
      (node (ref "A1") (pin "GPIO23") (pinfunction "GPIO23_GPIO23") (pintype "bidirectional"))
    )
    (net (code "66") (name "unconnected-(A1-RESET{slash}EN-PadEN)") (class "Default")
      (node (ref "A1") (pin "EN") (pinfunction "RESET/EN_EN") (pintype "bidirectional"))
    )
    (net (code "67") (name "unconnected-(A1-SCK_SPICLK_GPIO6-PadGPIO06)") (class "Default")
      (node (ref "A1") (pin "GPIO06") (pinfunction "SCK_SPICLK_GPIO6_GPIO06") (pintype "bidirectional"))
    )
    (net (code "68") (name "unconnected-(A1-U0RXD_CLK2_GPIO3-PadGPIO03)") (class "Default")
      (node (ref "A1") (pin "GPIO03") (pinfunction "U0RXD_CLK2_GPIO3_GPIO03") (pintype "bidirectional"))
    )
    (net (code "69") (name "unconnected-(A1-U0TXD_CLK3_GPIO1-PadGPIO01)") (class "Default")
      (node (ref "A1") (pin "GPIO01") (pinfunction "U0TXD_CLK3_GPIO1_GPIO01") (pintype "bidirectional"))
    )
    (net (code "70") (name "unconnected-(A1-U2RXD_GPIO16-PadGPIO16)") (class "Default")
      (node (ref "A1") (pin "GPIO16") (pinfunction "U2RXD_GPIO16_GPIO16") (pintype "bidirectional"))
    )
    (net (code "71") (name "unconnected-(A1-U2TXD_GPIO17-PadGPIO17)") (class "Default")
      (node (ref "A1") (pin "GPIO17") (pinfunction "U2TXD_GPIO17_GPIO17") (pintype "bidirectional"))
    )
    (net (code "72") (name "unconnected-(IC1-ALERT-Pad8)") (class "Default")
      (node (ref "IC1") (pin "8") (pinfunction "ALERT_8") (pintype "output"))
    )
    (net (code "73") (name "unconnected-(U1-CDC-Pad16)") (class "Default")
      (node (ref "U1") (pin "16") (pinfunction "CDC_16") (pintype "bidirectional"))
    )
    (net (code "74") (name "unconnected-(U1-DITH{slash}SYNC-Pad7)") (class "Default")
      (node (ref "U1") (pin "7") (pinfunction "DITH/SYNC_7") (pintype "input"))
    )
    (net (code "75") (name "unconnected-(X1-Pad2)") (class "Default")
      (node (ref "X1") (pin "2") (pinfunction "2_2") (pintype "passive"))
    )
  )
)
